# V1_2-.net
KiCad netlist of a schematic drawn in Altium Designer
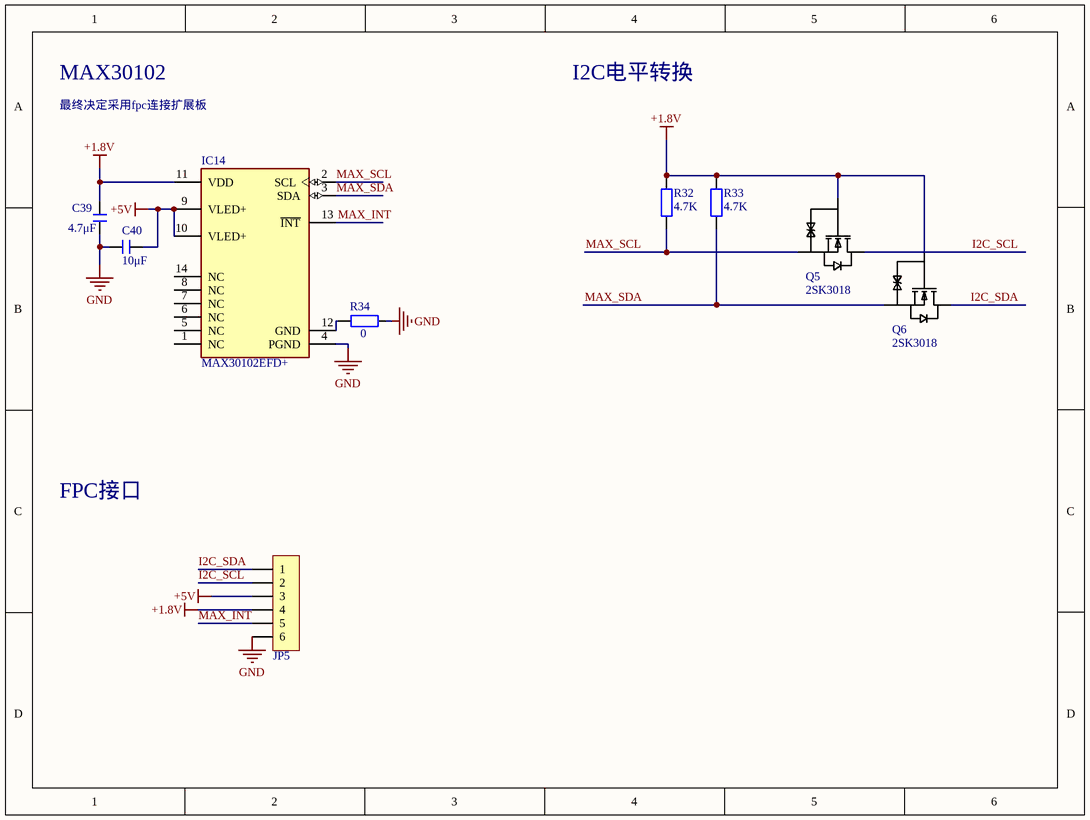
[diagram p0: V1.2-扩展板.SchDoc]

(export (version "E")
  (design (tool "Eeschema 10.0.6"))
  (components
    (comp (ref "C39")
      (value "4.7μF")
      (footprint "C 0603_L")
      (description "无极性贴片电容")
      (fields (field (name "版权归属") "源创客"))
      (libsource (lib "STM32_Watch") (part "C"))
    )
    (comp (ref "C40")
      (value "10μF")
      (footprint "C 0603_L")
      (description "无极性贴片电容")
      (fields (field (name "版权归属") "源创客"))
      (libsource (lib "STM32_Watch") (part "C"))
    )
    (comp (ref "IC14")
      (value "MAX30102EFD+")
      (footprint "FP-F143A5-1-MFG")
      (description "IC SENSOR OXIMETER/HEARTRATE")
      (fields
        (field (name "MANUFACTURER") "Maxim Integrated")
        (field (name "OCTOPART") "https://octopart.com/max30102efd%2B-maxim+integrated-59568799")
      )
      (libsource (lib "STM32_Watch") (part "MAX30102"))
    )
    (comp (ref "JP5")
      (value "FPC1.0-6P")
      (footprint "FPC0.5 2H-WS-6P")
      (description "FPC连接器")
      (fields (field (name "版权归属") "源创客"))
      (libsource (lib "STM32_Watch") (part "FPC-6P"))
    )
    (comp (ref "Q5")
      (value "2SK3018")
      (footprint "SOT23-3L")
      (fields (field (name "MANUFACTURER") "TWGMC(台湾迪嘉)"))
      (libsource (lib "STM32_Watch") (part "2SK3018"))
    )
    (comp (ref "Q6")
      (value "2SK3018")
      (footprint "SOT23-3L")
      (fields (field (name "MANUFACTURER") "TWGMC(台湾迪嘉)"))
      (libsource (lib "STM32_Watch") (part "2SK3018"))
    )
    (comp (ref "R32")
      (value "4.7K")
      (footprint "R 0603_L")
      (description "贴片电阻")
      (fields (field (name "版权归属") "源创客"))
      (libsource (lib "STM32_Watch") (part "R"))
    )
    (comp (ref "R33")
      (value "4.7K")
      (footprint "R 0603_L")
      (description "贴片电阻")
      (fields (field (name "版权归属") "源创客"))
      (libsource (lib "STM32_Watch") (part "R"))
    )
    (comp (ref "R34")
      (value "0")
      (footprint "R 0603_L")
      (description "贴片电阻")
      (fields (field (name "版权归属") "源创客"))
      (libsource (lib "STM32_Watch") (part "R"))
    )
  )
  (nets
    (net (code "1") (name "+1.8V") (class "Default")
      (node (ref "C39") (pin "1") (pinfunction "1_1") (pintype "passive"))
      (node (ref "IC14") (pin "11") (pinfunction "VDD_11") (pintype "power_in"))
      (node (ref "JP5") (pin "4") (pinfunction "4_4") (pintype "passive"))
      (node (ref "Q5") (pin "1") (pinfunction "G_1") (pintype "passive"))
      (node (ref "Q6") (pin "1") (pinfunction "G_1") (pintype "passive"))
      (node (ref "R32") (pin "1") (pinfunction "1_1") (pintype "passive"))
      (node (ref "R33") (pin "1") (pinfunction "1_1") (pintype "passive"))
    )
    (net (code "2") (name "+5V") (class "Default")
      (node (ref "C40") (pin "2") (pinfunction "2_2") (pintype "passive"))
      (node (ref "IC14") (pin "10") (pinfunction "VLED+_10") (pintype "power_in"))
      (node (ref "IC14") (pin "9") (pinfunction "VLED+_9") (pintype "power_in"))
      (node (ref "JP5") (pin "3") (pinfunction "3_3") (pintype "passive"))
    )
    (net (code "3") (name "/I2C_SCL") (class "Default")
      (node (ref "JP5") (pin "2") (pinfunction "2_2") (pintype "passive"))
      (node (ref "Q5") (pin "3") (pinfunction "D_3") (pintype "passive"))
    )
    (net (code "4") (name "/I2C_SDA") (class "Default")
      (node (ref "JP5") (pin "1") (pinfunction "1_1") (pintype "passive"))
      (node (ref "Q6") (pin "3") (pinfunction "D_3") (pintype "passive"))
    )
    (net (code "5") (name "/MAX_INT") (class "Default")
      (node (ref "IC14") (pin "13") (pinfunction "~{INT}_13") (pintype "open_collector"))
      (node (ref "JP5") (pin "5") (pinfunction "5_5") (pintype "passive"))
    )
    (net (code "6") (name "/MAX_SCL") (class "Default")
      (node (ref "IC14") (pin "2") (pinfunction "SCL_2") (pintype "bidirectional"))
      (node (ref "Q5") (pin "2") (pinfunction "S_2") (pintype "passive"))
      (node (ref "R32") (pin "2") (pinfunction "2_2") (pintype "passive"))
    )
    (net (code "7") (name "/MAX_SDA") (class "Default")
      (node (ref "IC14") (pin "3") (pinfunction "SDA_3") (pintype "bidirectional"))
      (node (ref "Q6") (pin "2") (pinfunction "S_2") (pintype "passive"))
      (node (ref "R33") (pin "2") (pinfunction "2_2") (pintype "passive"))
    )
    (net (code "8") (name "GND") (class "Default")
      (node (ref "C39") (pin "2") (pinfunction "2_2") (pintype "passive"))
      (node (ref "C40") (pin "1") (pinfunction "1_1") (pintype "passive"))
      (node (ref "IC14") (pin "4") (pinfunction "PGND_4") (pintype "power_in"))
      (node (ref "JP5") (pin "6") (pinfunction "6_6") (pintype "passive"))
      (node (ref "R34") (pin "1") (pinfunction "1_1") (pintype "passive"))
    )
    (net (code "9") (name "Net-(IC14-GND)") (class "Default")
      (node (ref "IC14") (pin "12") (pinfunction "GND_12") (pintype "power_in"))
      (node (ref "R34") (pin "2") (pinfunction "2_2") (pintype "passive"))
    )
    (net (code "10") (name "unconnected-(IC14-NC-Pad1)") (class "Default")
      (node (ref "IC14") (pin "1") (pinfunction "NC_1") (pintype "passive"))
    )
    (net (code "11") (name "unconnected-(IC14-NC-Pad5)") (class "Default")
      (node (ref "IC14") (pin "5") (pinfunction "NC_5") (pintype "passive"))
    )
    (net (code "12") (name "unconnected-(IC14-NC-Pad6)") (class "Default")
      (node (ref "IC14") (pin "6") (pinfunction "NC_6") (pintype "passive"))
    )
    (net (code "13") (name "unconnected-(IC14-NC-Pad7)") (class "Default")
      (node (ref "IC14") (pin "7") (pinfunction "NC_7") (pintype "passive"))
    )
    (net (code "14") (name "unconnected-(IC14-NC-Pad8)") (class "Default")
      (node (ref "IC14") (pin "8") (pinfunction "NC_8") (pintype "passive"))
    )
    (net (code "15") (name "unconnected-(IC14-NC-Pad14)") (class "Default")
      (node (ref "IC14") (pin "14") (pinfunction "NC_14") (pintype "passive"))
    )
  )
)
